# 17103448.net
KiCad netlist of a schematic drawn in EAGLE
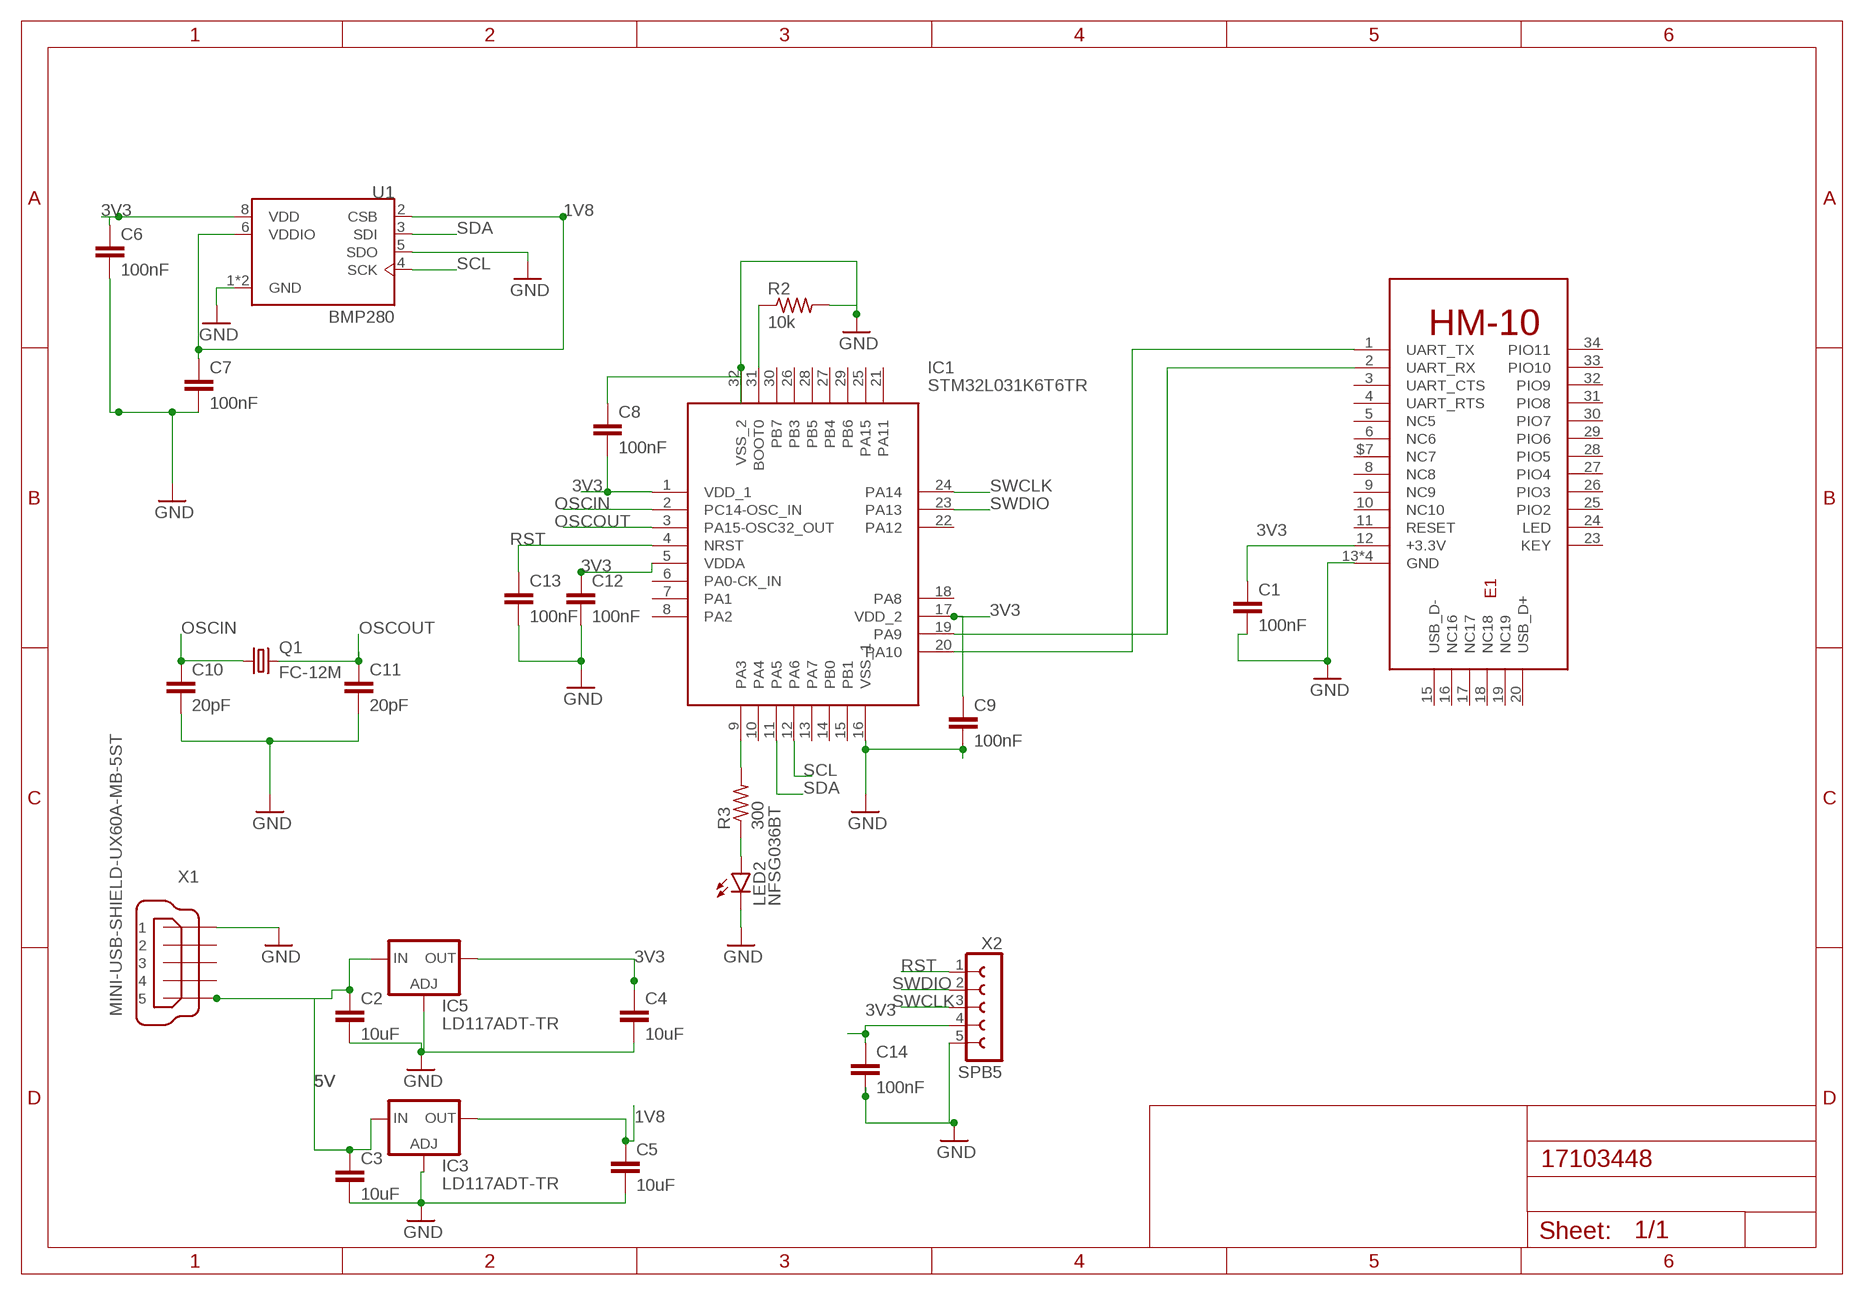
[diagram p0: schematic, sheet 1]

(export (version "E")
  (design (tool "Eeschema 10.0.6"))
  (components
    (comp (ref "C1")
      (value "100nF")
      (footprint "eagle-import:C0805")
      (libsource (lib "eagle-import") (part "C-EUC0805"))
    )
    (comp (ref "C2")
      (value "10uF")
      (footprint "eagle-import:C0805")
      (libsource (lib "eagle-import") (part "C-EUC0805"))
    )
    (comp (ref "C3")
      (value "10uF")
      (footprint "eagle-import:C0805")
      (libsource (lib "eagle-import") (part "C-EUC0805"))
    )
    (comp (ref "C4")
      (value "10uF")
      (footprint "eagle-import:C0805")
      (libsource (lib "eagle-import") (part "C-EUC0805"))
    )
    (comp (ref "C5")
      (value "10uF")
      (footprint "eagle-import:C0805")
      (libsource (lib "eagle-import") (part "C-EUC0805"))
    )
    (comp (ref "C6")
      (value "100nF")
      (footprint "eagle-import:C0805")
      (libsource (lib "eagle-import") (part "C-EUC0805"))
    )
    (comp (ref "C7")
      (value "100nF")
      (footprint "eagle-import:C0805")
      (libsource (lib "eagle-import") (part "C-EUC0805"))
    )
    (comp (ref "C8")
      (value "100nF")
      (footprint "eagle-import:C0805")
      (libsource (lib "eagle-import") (part "C-EUC0805"))
    )
    (comp (ref "C9")
      (value "100nF")
      (footprint "eagle-import:C0805")
      (libsource (lib "eagle-import") (part "C-EUC0805"))
    )
    (comp (ref "C10")
      (value "20pF")
      (footprint "eagle-import:C0805")
      (libsource (lib "eagle-import") (part "C-EUC0805"))
    )
    (comp (ref "C11")
      (value "20pF")
      (footprint "eagle-import:C0805")
      (libsource (lib "eagle-import") (part "C-EUC0805"))
    )
    (comp (ref "C12")
      (value "100nF")
      (footprint "eagle-import:C0805")
      (libsource (lib "eagle-import") (part "C-EUC0805"))
    )
    (comp (ref "C13")
      (value "100nF")
      (footprint "eagle-import:C0805")
      (libsource (lib "eagle-import") (part "C-EUC0805"))
    )
    (comp (ref "C14")
      (value "100nF")
      (footprint "eagle-import:C0805")
      (libsource (lib "eagle-import") (part "C-EUC0805"))
    )
    (comp (ref "E1")
      (value "HM-10-BOARD")
      (footprint "eagle-import:26.9X13X2.2_BOARD")
      (libsource (lib "eagle-import") (part "HM-10-BOARD"))
    )
    (comp (ref "IC1")
      (value "STM32L031K6T6TR")
      (footprint "eagle-import:QFP80P900X900X160-32N")
      (fields (field (name "MOUSER_PART_NUMBER") "511-STM32L031K6T6TR"))
      (libsource (lib "eagle-import") (part "STM32L031K6T6TR"))
    )
    (comp (ref "IC3")
      (value "LD117ADT-TR")
      (footprint "eagle-import:DPACK")
      (libsource (lib "eagle-import") (part "LD117A?DT-TR"))
    )
    (comp (ref "IC5")
      (value "LD117ADT-TR")
      (footprint "eagle-import:DPACK")
      (libsource (lib "eagle-import") (part "LD117A?DT-TR"))
    )
    (comp (ref "LED2")
      (value "NFSG036BT")
      (footprint "eagle-import:NFSG036BT")
      (libsource (lib "eagle-import") (part "NFSG036BT"))
    )
    (comp (ref "Q1")
      (value "FC-12M")
      (footprint "eagle-import:FC-12M")
      (libsource (lib "eagle-import") (part "FC-12M"))
    )
    (comp (ref "R2")
      (value "10k")
      (footprint "eagle-import:R0805")
      (libsource (lib "eagle-import") (part "R-US_R0805"))
    )
    (comp (ref "R3")
      (value "300")
      (footprint "eagle-import:R0805")
      (libsource (lib "eagle-import") (part "R-US_R0805"))
    )
    (comp (ref "U1")
      (value "BMP280")
      (footprint "eagle-import:XDCR_BMP280")
      (fields (field (name "MF") "Bosch"))
      (libsource (lib "eagle-import") (part "BMP280"))
    )
    (comp (ref "X1")
      (value "MINI-USB-SHIELD-UX60A-MB-5ST")
      (footprint "eagle-import:UX60A-MB-5ST")
      (libsource (lib "eagle-import") (part "MINI-USB-SHIELD-UX60A-MB-5ST"))
    )
    (comp (ref "X2")
      (value "SPB5")
      (footprint "eagle-import:SPB5")
      (libsource (lib "eagle-import") (part "SPB5"))
    )
  )
  (nets
    (net (code "1") (name "/1V8") (class "Default")
      (node (ref "C5") (pin "1") (pinfunction "1_1") (pintype "passive"))
      (node (ref "C7") (pin "1") (pinfunction "1_1") (pintype "passive"))
      (node (ref "IC3") (pin "4") (pinfunction "OUT_4") (pintype "passive"))
      (node (ref "U1") (pin "2") (pinfunction "CSB_2") (pintype "input"))
      (node (ref "U1") (pin "6") (pinfunction "VDDIO_6") (pintype "power_in"))
    )
    (net (code "2") (name "/3V3") (class "Default")
      (node (ref "C1") (pin "1") (pinfunction "1_1") (pintype "passive"))
      (node (ref "C12") (pin "1") (pinfunction "1_1") (pintype "passive"))
      (node (ref "C14") (pin "1") (pinfunction "1_1") (pintype "passive"))
      (node (ref "C4") (pin "1") (pinfunction "1_1") (pintype "passive"))
      (node (ref "C6") (pin "1") (pinfunction "1_1") (pintype "passive"))
      (node (ref "C8") (pin "2") (pinfunction "2_2") (pintype "passive"))
      (node (ref "C9") (pin "1") (pinfunction "1_1") (pintype "passive"))
      (node (ref "E1") (pin "12") (pinfunction "+3.3V_12") (pintype "bidirectional"))
      (node (ref "IC1") (pin "1") (pinfunction "VDD_1_1") (pintype "bidirectional"))
      (node (ref "IC1") (pin "17") (pinfunction "VDD_2_17") (pintype "bidirectional"))
      (node (ref "IC1") (pin "5") (pinfunction "VDDA_5") (pintype "bidirectional"))
      (node (ref "IC5") (pin "4") (pinfunction "OUT_4") (pintype "passive"))
      (node (ref "U1") (pin "8") (pinfunction "VDD_8") (pintype "power_in"))
      (node (ref "X2") (pin "4") (pinfunction "4_4") (pintype "passive"))
    )
    (net (code "3") (name "/5V") (class "Default")
      (node (ref "C2") (pin "1") (pinfunction "1_1") (pintype "passive"))
      (node (ref "C3") (pin "1") (pinfunction "1_1") (pintype "passive"))
      (node (ref "IC3") (pin "3") (pinfunction "IN_3") (pintype "input"))
      (node (ref "IC5") (pin "3") (pinfunction "IN_3") (pintype "input"))
      (node (ref "X1") (pin "5") (pinfunction "5_5") (pintype "input"))
    )
    (net (code "4") (name "/OSCIN") (class "Default")
      (node (ref "C10") (pin "1") (pinfunction "1_1") (pintype "passive"))
      (node (ref "IC1") (pin "2") (pinfunction "PC14-OSC_IN_2") (pintype "bidirectional"))
      (node (ref "Q1") (pin "1") (pinfunction "1_1") (pintype "passive"))
    )
    (net (code "5") (name "/OSCOUT") (class "Default")
      (node (ref "C11") (pin "1") (pinfunction "1_1") (pintype "passive"))
      (node (ref "IC1") (pin "3") (pinfunction "PA15-OSC32_OUT_3") (pintype "bidirectional"))
      (node (ref "Q1") (pin "2") (pinfunction "2_2") (pintype "passive"))
    )
    (net (code "6") (name "/RST") (class "Default")
      (node (ref "C13") (pin "1") (pinfunction "1_1") (pintype "passive"))
      (node (ref "IC1") (pin "4") (pinfunction "NRST_4") (pintype "bidirectional"))
      (node (ref "X2") (pin "1") (pinfunction "1_1") (pintype "passive"))
    )
    (net (code "7") (name "/SCL") (class "Default")
      (node (ref "IC1") (pin "12") (pinfunction "PA6_12") (pintype "bidirectional"))
      (node (ref "U1") (pin "4") (pinfunction "SCK_4") (pintype "input"))
    )
    (net (code "8") (name "/SDA") (class "Default")
      (node (ref "IC1") (pin "11") (pinfunction "PA5_11") (pintype "bidirectional"))
      (node (ref "U1") (pin "3") (pinfunction "SDI_3") (pintype "bidirectional"))
    )
    (net (code "9") (name "/SWCLK") (class "Default")
      (node (ref "IC1") (pin "24") (pinfunction "PA14_24") (pintype "bidirectional"))
      (node (ref "X2") (pin "3") (pinfunction "3_3") (pintype "passive"))
    )
    (net (code "10") (name "/SWDIO") (class "Default")
      (node (ref "IC1") (pin "23") (pinfunction "PA13_23") (pintype "bidirectional"))
      (node (ref "X2") (pin "2") (pinfunction "2_2") (pintype "passive"))
    )
    (net (code "11") (name "GND") (class "Default")
      (node (ref "C1") (pin "2") (pinfunction "2_2") (pintype "passive"))
      (node (ref "C10") (pin "2") (pinfunction "2_2") (pintype "passive"))
      (node (ref "C11") (pin "2") (pinfunction "2_2") (pintype "passive"))
      (node (ref "C12") (pin "2") (pinfunction "2_2") (pintype "passive"))
      (node (ref "C13") (pin "2") (pinfunction "2_2") (pintype "passive"))
      (node (ref "C14") (pin "2") (pinfunction "2_2") (pintype "passive"))
      (node (ref "C2") (pin "2") (pinfunction "2_2") (pintype "passive"))
      (node (ref "C3") (pin "2") (pinfunction "2_2") (pintype "passive"))
      (node (ref "C4") (pin "2") (pinfunction "2_2") (pintype "passive"))
      (node (ref "C5") (pin "2") (pinfunction "2_2") (pintype "passive"))
      (node (ref "C6") (pin "2") (pinfunction "2_2") (pintype "passive"))
      (node (ref "C7") (pin "2") (pinfunction "2_2") (pintype "passive"))
      (node (ref "C8") (pin "1") (pinfunction "1_1") (pintype "passive"))
      (node (ref "C9") (pin "2") (pinfunction "2_2") (pintype "passive"))
      (node (ref "E1") (pin "13") (pinfunction "GND_13") (pintype "bidirectional"))
      (node (ref "E1") (pin "14") (pinfunction "GND_14") (pintype "bidirectional"))
      (node (ref "E1") (pin "21") (pinfunction "GND_21") (pintype "bidirectional"))
      (node (ref "E1") (pin "22") (pinfunction "GND_22") (pintype "bidirectional"))
      (node (ref "IC1") (pin "16") (pinfunction "VSS_1_16") (pintype "bidirectional"))
      (node (ref "IC1") (pin "32") (pinfunction "VSS_2_32") (pintype "bidirectional"))
      (node (ref "IC3") (pin "1") (pinfunction "ADJ_1") (pintype "input"))
      (node (ref "IC5") (pin "1") (pinfunction "ADJ_1") (pintype "input"))
      (node (ref "LED2") (pin "C") (pinfunction "C_C") (pintype "passive"))
      (node (ref "R2") (pin "2") (pinfunction "2_2") (pintype "passive"))
      (node (ref "U1") (pin "1") (pinfunction "GND_1") (pintype "power_in"))
      (node (ref "U1") (pin "5") (pinfunction "SDO_5") (pintype "bidirectional"))
      (node (ref "U1") (pin "7") (pinfunction "GND_7") (pintype "power_in"))
      (node (ref "X1") (pin "1") (pinfunction "1_1") (pintype "input"))
      (node (ref "X2") (pin "5") (pinfunction "5_5") (pintype "passive"))
    )
    (net (code "12") (name "Net-(E1-UART_RX)") (class "Default")
      (node (ref "E1") (pin "2") (pinfunction "UART_RX_2") (pintype "bidirectional"))
      (node (ref "IC1") (pin "19") (pinfunction "PA9_19") (pintype "bidirectional"))
    )
    (net (code "13") (name "Net-(E1-UART_TX)") (class "Default")
      (node (ref "E1") (pin "1") (pinfunction "UART_TX_1") (pintype "bidirectional"))
      (node (ref "IC1") (pin "20") (pinfunction "PA10_20") (pintype "bidirectional"))
    )
    (net (code "14") (name "Net-(IC1-BOOT0)") (class "Default")
      (node (ref "IC1") (pin "31") (pinfunction "BOOT0_31") (pintype "bidirectional"))
      (node (ref "R2") (pin "1") (pinfunction "1_1") (pintype "passive"))
    )
    (net (code "15") (name "Net-(IC1-PA3)") (class "Default")
      (node (ref "IC1") (pin "9") (pinfunction "PA3_9") (pintype "bidirectional"))
      (node (ref "R3") (pin "2") (pinfunction "2_2") (pintype "passive"))
    )
    (net (code "16") (name "Net-(LED2-PadA)") (class "Default")
      (node (ref "LED2") (pin "A") (pinfunction "A_A") (pintype "passive"))
      (node (ref "R3") (pin "1") (pinfunction "1_1") (pintype "passive"))
    )
    (net (code "17") (name "unconnected-(E1-KEY-Pad23)") (class "Default")
      (node (ref "E1") (pin "23") (pinfunction "KEY_23") (pintype "bidirectional"))
    )
    (net (code "18") (name "unconnected-(E1-LED-Pad24)") (class "Default")
      (node (ref "E1") (pin "24") (pinfunction "LED_24") (pintype "bidirectional"))
    )
    (net (code "19") (name "unconnected-(E1-NC5-Pad5)") (class "Default")
      (node (ref "E1") (pin "5") (pinfunction "NC5_5") (pintype "bidirectional"))
    )
    (net (code "20") (name "unconnected-(E1-NC6-Pad6)") (class "Default")
      (node (ref "E1") (pin "6") (pinfunction "NC6_6") (pintype "bidirectional"))
    )
    (net (code "21") (name "unconnected-(E1-NC7-Pad$7)") (class "Default")
      (node (ref "E1") (pin "$7") (pinfunction "NC7_$7") (pintype "bidirectional"))
    )
    (net (code "22") (name "unconnected-(E1-NC8-Pad8)") (class "Default")
      (node (ref "E1") (pin "8") (pinfunction "NC8_8") (pintype "bidirectional"))
    )
    (net (code "23") (name "unconnected-(E1-NC9-Pad9)") (class "Default")
      (node (ref "E1") (pin "9") (pinfunction "NC9_9") (pintype "bidirectional"))
    )
    (net (code "24") (name "unconnected-(E1-NC10-Pad10)") (class "Default")
      (node (ref "E1") (pin "10") (pinfunction "NC10_10") (pintype "bidirectional"))
    )
    (net (code "25") (name "unconnected-(E1-NC16-Pad16)") (class "Default")
      (node (ref "E1") (pin "16") (pinfunction "NC16_16") (pintype "bidirectional"))
    )
    (net (code "26") (name "unconnected-(E1-NC17-Pad17)") (class "Default")
      (node (ref "E1") (pin "17") (pinfunction "NC17_17") (pintype "bidirectional"))
    )
    (net (code "27") (name "unconnected-(E1-NC18-Pad18)") (class "Default")
      (node (ref "E1") (pin "18") (pinfunction "NC18_18") (pintype "bidirectional"))
    )
    (net (code "28") (name "unconnected-(E1-NC19-Pad19)") (class "Default")
      (node (ref "E1") (pin "19") (pinfunction "NC19_19") (pintype "bidirectional"))
    )
    (net (code "29") (name "unconnected-(E1-PIO2-Pad25)") (class "Default")
      (node (ref "E1") (pin "25") (pinfunction "PIO2_25") (pintype "bidirectional"))
    )
    (net (code "30") (name "unconnected-(E1-PIO3-Pad26)") (class "Default")
      (node (ref "E1") (pin "26") (pinfunction "PIO3_26") (pintype "bidirectional"))
    )
    (net (code "31") (name "unconnected-(E1-PIO4-Pad27)") (class "Default")
      (node (ref "E1") (pin "27") (pinfunction "PIO4_27") (pintype "bidirectional"))
    )
    (net (code "32") (name "unconnected-(E1-PIO5-Pad28)") (class "Default")
      (node (ref "E1") (pin "28") (pinfunction "PIO5_28") (pintype "bidirectional"))
    )
    (net (code "33") (name "unconnected-(E1-PIO6-Pad29)") (class "Default")
      (node (ref "E1") (pin "29") (pinfunction "PIO6_29") (pintype "bidirectional"))
    )
    (net (code "34") (name "unconnected-(E1-PIO7-Pad30)") (class "Default")
      (node (ref "E1") (pin "30") (pinfunction "PIO7_30") (pintype "bidirectional"))
    )
    (net (code "35") (name "unconnected-(E1-PIO8-Pad31)") (class "Default")
      (node (ref "E1") (pin "31") (pinfunction "PIO8_31") (pintype "bidirectional"))
    )
    (net (code "36") (name "unconnected-(E1-PIO9-Pad32)") (class "Default")
      (node (ref "E1") (pin "32") (pinfunction "PIO9_32") (pintype "bidirectional"))
    )
    (net (code "37") (name "unconnected-(E1-PIO10-Pad33)") (class "Default")
      (node (ref "E1") (pin "33") (pinfunction "PIO10_33") (pintype "bidirectional"))
    )
    (net (code "38") (name "unconnected-(E1-PIO11-Pad34)") (class "Default")
      (node (ref "E1") (pin "34") (pinfunction "PIO11_34") (pintype "bidirectional"))
    )
    (net (code "39") (name "unconnected-(E1-RESET-Pad11)") (class "Default")
      (node (ref "E1") (pin "11") (pinfunction "RESET_11") (pintype "bidirectional"))
    )
    (net (code "40") (name "unconnected-(E1-UART_CTS-Pad3)") (class "Default")
      (node (ref "E1") (pin "3") (pinfunction "UART_CTS_3") (pintype "bidirectional"))
    )
    (net (code "41") (name "unconnected-(E1-UART_RTS-Pad4)") (class "Default")
      (node (ref "E1") (pin "4") (pinfunction "UART_RTS_4") (pintype "bidirectional"))
    )
    (net (code "42") (name "unconnected-(E1-USB_D+-Pad20)") (class "Default")
      (node (ref "E1") (pin "20") (pinfunction "USB_D+_20") (pintype "bidirectional"))
    )
    (net (code "43") (name "unconnected-(E1-USB_D--Pad15)") (class "Default")
      (node (ref "E1") (pin "15") (pinfunction "USB_D-_15") (pintype "bidirectional"))
    )
    (net (code "44") (name "unconnected-(IC1-PA0-CK_IN-Pad6)") (class "Default")
      (node (ref "IC1") (pin "6") (pinfunction "PA0-CK_IN_6") (pintype "bidirectional"))
    )
    (net (code "45") (name "unconnected-(IC1-PA1-Pad7)") (class "Default")
      (node (ref "IC1") (pin "7") (pinfunction "PA1_7") (pintype "bidirectional"))
    )
    (net (code "46") (name "unconnected-(IC1-PA2-Pad8)") (class "Default")
      (node (ref "IC1") (pin "8") (pinfunction "PA2_8") (pintype "bidirectional"))
    )
    (net (code "47") (name "unconnected-(IC1-PA4-Pad10)") (class "Default")
      (node (ref "IC1") (pin "10") (pinfunction "PA4_10") (pintype "bidirectional"))
    )
    (net (code "48") (name "unconnected-(IC1-PA7-Pad13)") (class "Default")
      (node (ref "IC1") (pin "13") (pinfunction "PA7_13") (pintype "bidirectional"))
    )
    (net (code "49") (name "unconnected-(IC1-PA8-Pad18)") (class "Default")
      (node (ref "IC1") (pin "18") (pinfunction "PA8_18") (pintype "bidirectional"))
    )
    (net (code "50") (name "unconnected-(IC1-PA11-Pad21)") (class "Default")
      (node (ref "IC1") (pin "21") (pinfunction "PA11_21") (pintype "bidirectional"))
    )
    (net (code "51") (name "unconnected-(IC1-PA12-Pad22)") (class "Default")
      (node (ref "IC1") (pin "22") (pinfunction "PA12_22") (pintype "bidirectional"))
    )
    (net (code "52") (name "unconnected-(IC1-PA15-Pad25)") (class "Default")
      (node (ref "IC1") (pin "25") (pinfunction "PA15_25") (pintype "bidirectional"))
    )
    (net (code "53") (name "unconnected-(IC1-PB0-Pad14)") (class "Default")
      (node (ref "IC1") (pin "14") (pinfunction "PB0_14") (pintype "bidirectional"))
    )
    (net (code "54") (name "unconnected-(IC1-PB1-Pad15)") (class "Default")
      (node (ref "IC1") (pin "15") (pinfunction "PB1_15") (pintype "bidirectional"))
    )
    (net (code "55") (name "unconnected-(IC1-PB3-Pad26)") (class "Default")
      (node (ref "IC1") (pin "26") (pinfunction "PB3_26") (pintype "bidirectional"))
    )
    (net (code "56") (name "unconnected-(IC1-PB4-Pad27)") (class "Default")
      (node (ref "IC1") (pin "27") (pinfunction "PB4_27") (pintype "bidirectional"))
    )
    (net (code "57") (name "unconnected-(IC1-PB5-Pad28)") (class "Default")
      (node (ref "IC1") (pin "28") (pinfunction "PB5_28") (pintype "bidirectional"))
    )
    (net (code "58") (name "unconnected-(IC1-PB6-Pad29)") (class "Default")
      (node (ref "IC1") (pin "29") (pinfunction "PB6_29") (pintype "bidirectional"))
    )
    (net (code "59") (name "unconnected-(IC1-PB7-Pad30)") (class "Default")
      (node (ref "IC1") (pin "30") (pinfunction "PB7_30") (pintype "bidirectional"))
    )
    (net (code "60") (name "unconnected-(X1-Pad2)") (class "Default")
      (node (ref "X1") (pin "2") (pinfunction "2_2") (pintype "input"))
    )
    (net (code "61") (name "unconnected-(X1-Pad3)") (class "Default")
      (node (ref "X1") (pin "3") (pinfunction "3_3") (pintype "input"))
    )
    (net (code "62") (name "unconnected-(X1-Pad4)") (class "Default")
      (node (ref "X1") (pin "4") (pinfunction "4_4") (pintype "input"))
    )
  )
)
